# board.net
KiCad netlist of a schematic drawn in EAGLE
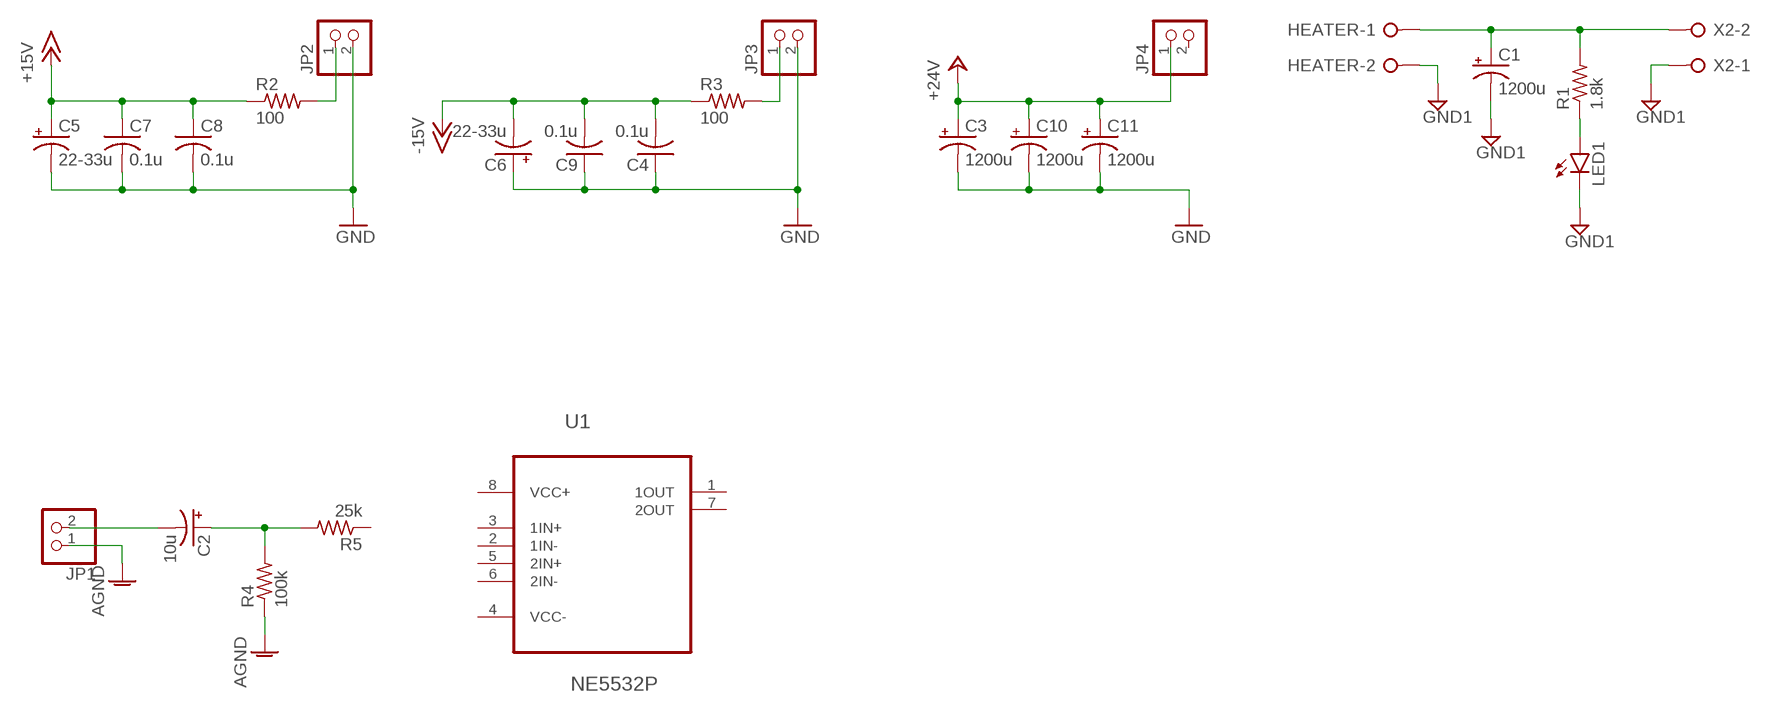
[diagram p0: schematic, sheet 1]

(export (version "E")
  (design (tool "Eeschema 10.0.6"))
  (components
    (comp (ref "C1")
      (value "1200u")
      (footprint "eagle-import:E7,5-18")
      (libsource (lib "eagle-import") (part "CPOL-USE7.5-18"))
    )
    (comp (ref "C2")
      (value "10u")
      (footprint "eagle-import:E2,5-7")
      (libsource (lib "eagle-import") (part "CPOL-USE2.5-7"))
    )
    (comp (ref "C3")
      (value "1200u")
      (footprint "eagle-import:E7,5-18")
      (libsource (lib "eagle-import") (part "CPOL-USE7.5-18"))
    )
    (comp (ref "C4")
      (value "0.1u")
      (footprint "eagle-import:C1206")
      (libsource (lib "eagle-import") (part "C-USC1206"))
    )
    (comp (ref "C5")
      (value "22-33u")
      (footprint "eagle-import:E2-5")
      (libsource (lib "eagle-import") (part "CPOL-USE2-5"))
    )
    (comp (ref "C6")
      (value "22-33u")
      (footprint "eagle-import:E2-5")
      (libsource (lib "eagle-import") (part "CPOL-USE2-5"))
    )
    (comp (ref "C7")
      (value "0.1u")
      (footprint "eagle-import:C1206")
      (libsource (lib "eagle-import") (part "C-USC1206"))
    )
    (comp (ref "C8")
      (value "0.1u")
      (footprint "eagle-import:C1206")
      (libsource (lib "eagle-import") (part "C-USC1206"))
    )
    (comp (ref "C9")
      (value "0.1u")
      (footprint "eagle-import:C1206")
      (libsource (lib "eagle-import") (part "C-USC1206"))
    )
    (comp (ref "C10")
      (value "1200u")
      (footprint "eagle-import:E7,5-18")
      (libsource (lib "eagle-import") (part "CPOL-USE7.5-18"))
    )
    (comp (ref "C11")
      (value "1200u")
      (footprint "eagle-import:E7,5-18")
      (libsource (lib "eagle-import") (part "CPOL-USE7.5-18"))
    )
    (comp (ref "HEATER")
      (value "W237-02P")
      (footprint "eagle-import:W237-132")
      (libsource (lib "eagle-import") (part "W237-02P"))
    )
    (comp (ref "JP1")
      (value "PINHD-1X2")
      (footprint "eagle-import:1X02")
      (libsource (lib "eagle-import") (part "PINHD-1X2"))
    )
    (comp (ref "JP2")
      (value "PINHD-1X2")
      (footprint "eagle-import:1X02")
      (libsource (lib "eagle-import") (part "PINHD-1X2"))
    )
    (comp (ref "JP3")
      (value "PINHD-1X2")
      (footprint "eagle-import:1X02")
      (libsource (lib "eagle-import") (part "PINHD-1X2"))
    )
    (comp (ref "JP4")
      (value "PINHD-1X2")
      (footprint "eagle-import:1X02")
      (libsource (lib "eagle-import") (part "PINHD-1X2"))
    )
    (comp (ref "LED1")
      (value "LED1206")
      (footprint "eagle-import:LED-1206")
      (libsource (lib "eagle-import") (part "LED1206"))
    )
    (comp (ref "R1")
      (value "1.8k")
      (footprint "eagle-import:R1206")
      (libsource (lib "eagle-import") (part "R-US_R1206"))
    )
    (comp (ref "R2")
      (value "100")
      (footprint "eagle-import:0207_7")
      (libsource (lib "eagle-import") (part "R-US_0207/7"))
    )
    (comp (ref "R3")
      (value "100")
      (footprint "eagle-import:0207_7")
      (libsource (lib "eagle-import") (part "R-US_0207/7"))
    )
    (comp (ref "R4")
      (value "100k")
      (footprint "eagle-import:0207_7")
      (libsource (lib "eagle-import") (part "R-US_0207/7"))
    )
    (comp (ref "R5")
      (value "25k")
      (footprint "eagle-import:0207_7")
      (libsource (lib "eagle-import") (part "R-US_0207/7"))
    )
    (comp (ref "U1")
      (value "NE5532P")
      (footprint "eagle-import:DIP254P762X508-8")
      (libsource (lib "eagle-import") (part "NE5532P"))
    )
    (comp (ref "X2")
      (value "W237-02P")
      (footprint "eagle-import:W237-132")
      (libsource (lib "eagle-import") (part "W237-02P"))
    )
  )
  (nets
    (net (code "1") (name "+15V") (class "Default")
      (node (ref "C5") (pin "+") (pinfunction "+_+") (pintype "passive"))
      (node (ref "C7") (pin "1") (pinfunction "1_1") (pintype "passive"))
      (node (ref "C8") (pin "1") (pinfunction "1_1") (pintype "passive"))
      (node (ref "R2") (pin "1") (pinfunction "1_1") (pintype "passive"))
    )
    (net (code "2") (name "+24V") (class "Default")
      (node (ref "C10") (pin "+") (pinfunction "+_+") (pintype "passive"))
      (node (ref "C11") (pin "+") (pinfunction "+_+") (pintype "passive"))
      (node (ref "C3") (pin "+") (pinfunction "+_+") (pintype "passive"))
      (node (ref "JP4") (pin "1") (pinfunction "1_1") (pintype "passive"))
    )
    (net (code "3") (name "-15V") (class "Default")
      (node (ref "C4") (pin "2") (pinfunction "2_2") (pintype "passive"))
      (node (ref "C6") (pin "-") (pinfunction "-_-") (pintype "passive"))
      (node (ref "C9") (pin "2") (pinfunction "2_2") (pintype "passive"))
      (node (ref "R3") (pin "1") (pinfunction "1_1") (pintype "passive"))
    )
    (net (code "4") (name "/VCC+") (class "Default")
      (node (ref "U1") (pin "8") (pinfunction "VCC+_8") (pintype "power_in"))
    )
    (net (code "5") (name "/VCC-") (class "Default")
      (node (ref "U1") (pin "4") (pinfunction "VCC-_4") (pintype "power_in"))
    )
    (net (code "6") (name "AGND") (class "Default")
      (node (ref "JP1") (pin "1") (pinfunction "1_1") (pintype "passive"))
      (node (ref "R4") (pin "1") (pinfunction "1_1") (pintype "passive"))
    )
    (net (code "7") (name "GND") (class "Default")
      (node (ref "C10") (pin "-") (pinfunction "-_-") (pintype "passive"))
      (node (ref "C11") (pin "-") (pinfunction "-_-") (pintype "passive"))
      (node (ref "C3") (pin "-") (pinfunction "-_-") (pintype "passive"))
      (node (ref "C4") (pin "1") (pinfunction "1_1") (pintype "passive"))
      (node (ref "C5") (pin "-") (pinfunction "-_-") (pintype "passive"))
      (node (ref "C6") (pin "+") (pinfunction "+_+") (pintype "passive"))
      (node (ref "C7") (pin "2") (pinfunction "2_2") (pintype "passive"))
      (node (ref "C8") (pin "2") (pinfunction "2_2") (pintype "passive"))
      (node (ref "C9") (pin "1") (pinfunction "1_1") (pintype "passive"))
      (node (ref "JP2") (pin "2") (pinfunction "2_2") (pintype "passive"))
      (node (ref "JP3") (pin "2") (pinfunction "2_2") (pintype "passive"))
    )
    (net (code "8") (name "GND1") (class "Default")
      (node (ref "C1") (pin "-") (pinfunction "-_-") (pintype "passive"))
      (node (ref "HEATER") (pin "2") (pinfunction "KL_2") (pintype "passive"))
      (node (ref "LED1") (pin "C") (pinfunction "C_C") (pintype "passive"))
      (node (ref "X2") (pin "1") (pinfunction "KL_1") (pintype "passive"))
    )
    (net (code "9") (name "Net-(C2-Pad+)") (class "Default")
      (node (ref "C2") (pin "+") (pinfunction "+_+") (pintype "passive"))
      (node (ref "R4") (pin "2") (pinfunction "2_2") (pintype "passive"))
      (node (ref "R5") (pin "2") (pinfunction "2_2") (pintype "passive"))
    )
    (net (code "10") (name "Net-(C2-Pad-)") (class "Default")
      (node (ref "C2") (pin "-") (pinfunction "-_-") (pintype "passive"))
      (node (ref "JP1") (pin "2") (pinfunction "2_2") (pintype "passive"))
    )
    (net (code "11") (name "Net-(HEATERA-KL)") (class "Default")
      (node (ref "C1") (pin "+") (pinfunction "+_+") (pintype "passive"))
      (node (ref "HEATER") (pin "1") (pinfunction "KL_1") (pintype "passive"))
      (node (ref "R1") (pin "2") (pinfunction "2_2") (pintype "passive"))
      (node (ref "X2") (pin "2") (pinfunction "KL_2") (pintype "passive"))
    )
    (net (code "12") (name "Net-(JP2-Pad1)") (class "Default")
      (node (ref "JP2") (pin "1") (pinfunction "1_1") (pintype "passive"))
      (node (ref "R2") (pin "2") (pinfunction "2_2") (pintype "passive"))
    )
    (net (code "13") (name "Net-(JP3-Pad1)") (class "Default")
      (node (ref "JP3") (pin "1") (pinfunction "1_1") (pintype "passive"))
      (node (ref "R3") (pin "2") (pinfunction "2_2") (pintype "passive"))
    )
    (net (code "14") (name "Net-(LED1-PadA)") (class "Default")
      (node (ref "LED1") (pin "A") (pinfunction "A_A") (pintype "passive"))
      (node (ref "R1") (pin "1") (pinfunction "1_1") (pintype "passive"))
    )
    (net (code "15") (name "unconnected-(JP4-Pad2)") (class "Default")
      (node (ref "JP4") (pin "2") (pinfunction "2_2") (pintype "passive"))
    )
    (net (code "16") (name "unconnected-(R5-Pad1)") (class "Default")
      (node (ref "R5") (pin "1") (pinfunction "1_1") (pintype "passive"))
    )
    (net (code "17") (name "unconnected-(U1-1IN+-Pad3)") (class "Default")
      (node (ref "U1") (pin "3") (pinfunction "1IN+_3") (pintype "input"))
    )
    (net (code "18") (name "unconnected-(U1-1IN--Pad2)") (class "Default")
      (node (ref "U1") (pin "2") (pinfunction "1IN-_2") (pintype "input"))
    )
    (net (code "19") (name "unconnected-(U1-1OUT-Pad1)") (class "Default")
      (node (ref "U1") (pin "1") (pinfunction "1OUT_1") (pintype "output"))
    )
    (net (code "20") (name "unconnected-(U1-2IN+-Pad5)") (class "Default")
      (node (ref "U1") (pin "5") (pinfunction "2IN+_5") (pintype "input"))
    )
    (net (code "21") (name "unconnected-(U1-2IN--Pad6)") (class "Default")
      (node (ref "U1") (pin "6") (pinfunction "2IN-_6") (pintype "input"))
    )
    (net (code "22") (name "unconnected-(U1-2OUT-Pad7)") (class "Default")
      (node (ref "U1") (pin "7") (pinfunction "2OUT_7") (pintype "output"))
    )
  )
)
